# DE-290817_03.net
KiCad netlist of a schematic drawn in Altium Designer
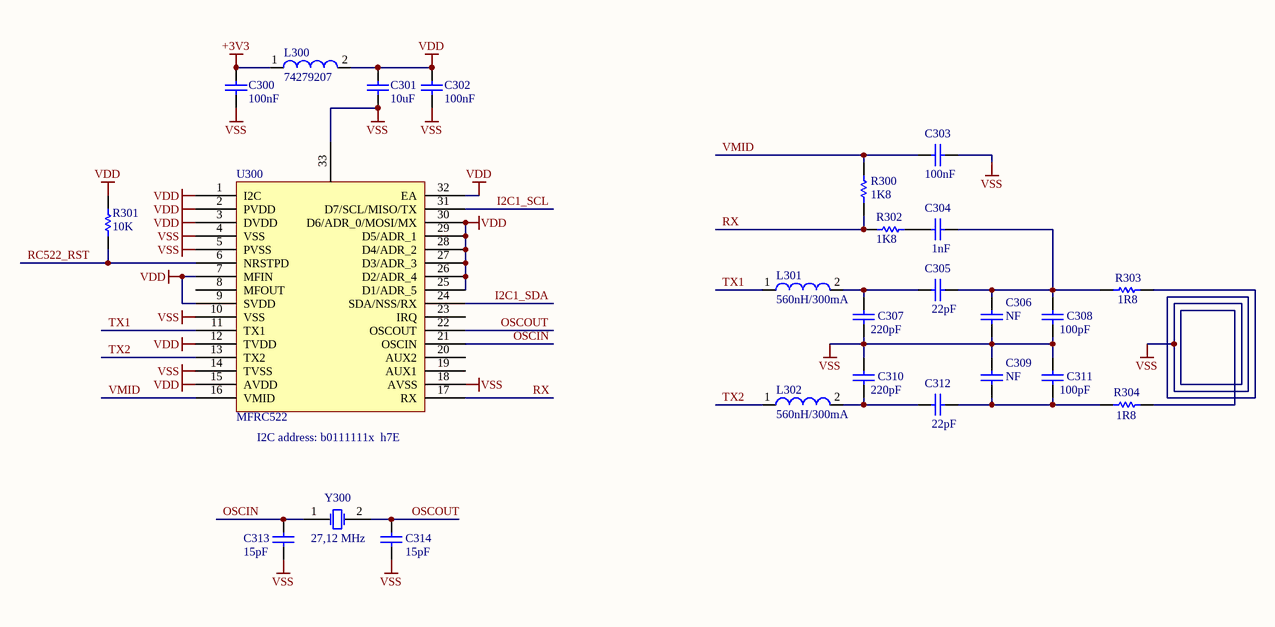
[diagram p0: DE-290817_03.SchDoc]

(export (version "E")
  (design (tool "Eeschema 10.0.6"))
  (components
    (comp (ref "C300")
      (value "100nF")
      (footprint "0603")
      (description "Ceramic Chip Capacitor - Standard")
      (fields (field (name "PUBLISHER") "Altium Limited"))
      (libsource (lib "KEMET Chip Capacitor") (part "C0603"))
    )
    (comp (ref "C301")
      (value "10uF")
      (footprint "0805")
      (description "Ceramic Chip Capacitor - Standard")
      (fields (field (name "PUBLISHER") "Altium Limited"))
      (libsource (lib "KEMET Chip Capacitor") (part "C0805"))
    )
    (comp (ref "C302")
      (value "100nF")
      (footprint "0603")
      (description "Ceramic Chip Capacitor - Standard")
      (fields (field (name "PUBLISHER") "Altium Limited"))
      (libsource (lib "KEMET Chip Capacitor") (part "C0603"))
    )
    (comp (ref "C303")
      (value "100nF")
      (footprint "0603")
      (description "Ceramic Chip Capacitor - Standard")
      (fields (field (name "PUBLISHER") "Altium Limited"))
      (libsource (lib "KEMET Chip Capacitor") (part "C0603"))
    )
    (comp (ref "C304")
      (value "1nF")
      (footprint "0603")
      (description "Ceramic Chip Capacitor - Standard")
      (fields (field (name "PUBLISHER") "Altium Limited"))
      (libsource (lib "KEMET Chip Capacitor") (part "C0603"))
    )
    (comp (ref "C305")
      (value "22pF")
      (footprint "0603")
      (description "Ceramic Chip Capacitor - Standard")
      (fields (field (name "PUBLISHER") "Altium Limited"))
      (libsource (lib "KEMET Chip Capacitor") (part "C0603"))
    )
    (comp (ref "C306")
      (value "NF")
      (footprint "0603")
      (description "Ceramic Chip Capacitor - Standard")
      (fields (field (name "PUBLISHER") "Altium Limited"))
      (libsource (lib "KEMET Chip Capacitor") (part "C0603"))
    )
    (comp (ref "C307")
      (value "220pF")
      (footprint "0603")
      (description "Ceramic Chip Capacitor - Standard")
      (fields (field (name "PUBLISHER") "Altium Limited"))
      (libsource (lib "KEMET Chip Capacitor") (part "C0603"))
    )
    (comp (ref "C308")
      (value "100pF")
      (footprint "0603")
      (description "Ceramic Chip Capacitor - Standard")
      (fields (field (name "PUBLISHER") "Altium Limited"))
      (libsource (lib "KEMET Chip Capacitor") (part "C0603"))
    )
    (comp (ref "C309")
      (value "NF")
      (footprint "0603")
      (description "Ceramic Chip Capacitor - Standard")
      (fields (field (name "PUBLISHER") "Altium Limited"))
      (libsource (lib "KEMET Chip Capacitor") (part "C0603"))
    )
    (comp (ref "C310")
      (value "220pF")
      (footprint "0603")
      (description "Ceramic Chip Capacitor - Standard")
      (fields (field (name "PUBLISHER") "Altium Limited"))
      (libsource (lib "KEMET Chip Capacitor") (part "C0603"))
    )
    (comp (ref "C311")
      (value "100pF")
      (footprint "0603")
      (description "Ceramic Chip Capacitor - Standard")
      (fields (field (name "PUBLISHER") "Altium Limited"))
      (libsource (lib "KEMET Chip Capacitor") (part "C0603"))
    )
    (comp (ref "C312")
      (value "22pF")
      (footprint "0603")
      (description "Ceramic Chip Capacitor - Standard")
      (fields (field (name "PUBLISHER") "Altium Limited"))
      (libsource (lib "KEMET Chip Capacitor") (part "C0603"))
    )
    (comp (ref "C313")
      (value "15pF")
      (footprint "0603")
      (description "Ceramic Chip Capacitor - Standard")
      (fields (field (name "PUBLISHER") "Altium Limited"))
      (libsource (lib "KEMET Chip Capacitor") (part "C0603"))
    )
    (comp (ref "C314")
      (value "15pF")
      (footprint "0603")
      (description "Ceramic Chip Capacitor - Standard")
      (fields (field (name "PUBLISHER") "Altium Limited"))
      (libsource (lib "KEMET Chip Capacitor") (part "C0603"))
    )
    (comp (ref "L300")
      (value "74279207")
      (footprint "SMD-0805")
      (description "SMD EMI Suppression Ferrite Bead WE-CBF, Z = 100 Ohm")
      (libsource (lib "WE-CBF SMD EMI Suppression Ferrite Bead") (part "74279207"))
    )
    (comp (ref "L301")
      (value "560nH/300mA")
      (footprint "SMD-0805")
      (description "SMD EMI Suppression Ferrite Bead WE-CBF, Z = 100 Ohm")
      (fields (field (name "PARTNUMBER") "74279207"))
      (libsource (lib "WE-CBF SMD EMI Suppression Ferrite Bead") (part "74279207"))
    )
    (comp (ref "L302")
      (value "560nH/300mA")
      (footprint "SMD-0805")
      (description "SMD EMI Suppression Ferrite Bead WE-CBF, Z = 100 Ohm")
      (fields (field (name "PARTNUMBER") "74279207"))
      (libsource (lib "WE-CBF SMD EMI Suppression Ferrite Bead") (part "74279207"))
    )
    (comp (ref "R300")
      (value "1K8")
      (footprint "3-0603")
      (fields (field (name "PUBLISHER") "Altium Limited"))
      (libsource (lib "Panasonic Resistor") (part "ERJ3RS"))
    )
    (comp (ref "R301")
      (value "10K")
      (footprint "ERA-0603")
      (fields (field (name "PUBLISHER") "Altium Limited"))
      (libsource (lib "DE-290817") (part "ERAV"))
    )
    (comp (ref "R302")
      (value "1K8")
      (footprint "3-0603")
      (fields (field (name "PUBLISHER") "Altium Limited"))
      (libsource (lib "Panasonic Resistor") (part "ERJ3RS"))
    )
    (comp (ref "R303")
      (value "1R8")
      (footprint "3-0603")
      (fields (field (name "PUBLISHER") "Altium Limited"))
      (libsource (lib "Panasonic Resistor") (part "ERJ3RS"))
    )
    (comp (ref "R304")
      (value "1R8")
      (footprint "3-0603")
      (fields (field (name "PUBLISHER") "Altium Limited"))
      (libsource (lib "Panasonic Resistor") (part "ERJ3RS"))
    )
    (comp (ref "U300")
      (value "MFRC522")
      (footprint "QFN32")
      (description "MIFARE reader writer")
      (libsource (lib "DE-071116") (part "MFRC522"))
    )
    (comp (ref "Y300")
      (value "27,12 MHz")
      (footprint "HC49/4H_SMX")
      (description "Crystal Oscillator")
      (fields (field (name "PUBLISHER") "Altium Limited"))
      (libsource (lib "ECS Crystal Oscillator") (part "ECS-80-20-1"))
    )
  )
  (nets
    (net (code "1") (name "+3V3") (class "Default")
      (node (ref "C300") (pin "2") (pinfunction "2_2") (pintype "passive"))
      (node (ref "L300") (pin "1") (pinfunction "1_1") (pintype "passive"))
    )
    (net (code "2") (name "/I2C1_SCL") (class "Default")
      (node (ref "U300") (pin "31") (pinfunction "D7/SCL/MISO/TX_31") (pintype "passive"))
    )
    (net (code "3") (name "/I2C1_SDA") (class "Default")
      (node (ref "U300") (pin "24") (pinfunction "SDA/NSS/RX_24") (pintype "passive"))
    )
    (net (code "4") (name "/OSCIN") (class "Default")
      (node (ref "C313") (pin "2") (pinfunction "2_2") (pintype "passive"))
      (node (ref "U300") (pin "21") (pinfunction "OSCIN_21") (pintype "passive"))
      (node (ref "Y300") (pin "1") (pinfunction "OSC1_1") (pintype "passive"))
    )
    (net (code "5") (name "/OSCOUT") (class "Default")
      (node (ref "C314") (pin "2") (pinfunction "2_2") (pintype "passive"))
      (node (ref "U300") (pin "22") (pinfunction "OSCOUT_22") (pintype "passive"))
      (node (ref "Y300") (pin "2") (pinfunction "OSC2_2") (pintype "passive"))
    )
    (net (code "6") (name "/RC522_RST") (class "Default")
      (node (ref "R301") (pin "1") (pinfunction "1_1") (pintype "passive"))
      (node (ref "U300") (pin "6") (pinfunction "NRSTPD_6") (pintype "passive"))
    )
    (net (code "7") (name "/RX") (class "Default")
      (node (ref "R300") (pin "2") (pinfunction "2_2") (pintype "passive"))
      (node (ref "R302") (pin "2") (pinfunction "2_2") (pintype "passive"))
      (node (ref "U300") (pin "17") (pinfunction "RX_17") (pintype "passive"))
    )
    (net (code "8") (name "/TX1") (class "Default")
      (node (ref "L301") (pin "1") (pinfunction "1_1") (pintype "passive"))
      (node (ref "U300") (pin "11") (pinfunction "TX1_11") (pintype "passive"))
    )
    (net (code "9") (name "/TX2") (class "Default")
      (node (ref "L302") (pin "1") (pinfunction "1_1") (pintype "passive"))
      (node (ref "U300") (pin "13") (pinfunction "TX2_13") (pintype "passive"))
    )
    (net (code "10") (name "/VMID") (class "Default")
      (node (ref "C303") (pin "2") (pinfunction "2_2") (pintype "passive"))
      (node (ref "R300") (pin "1") (pinfunction "1_1") (pintype "passive"))
      (node (ref "U300") (pin "16") (pinfunction "VMID_16") (pintype "passive"))
    )
    (net (code "11") (name "Net-(C304-Pad1)") (class "Default")
      (node (ref "C304") (pin "1") (pinfunction "1_1") (pintype "passive"))
      (node (ref "C305") (pin "1") (pinfunction "1_1") (pintype "passive"))
      (node (ref "C306") (pin "2") (pinfunction "2_2") (pintype "passive"))
      (node (ref "C308") (pin "2") (pinfunction "2_2") (pintype "passive"))
      (node (ref "R303") (pin "2") (pinfunction "2_2") (pintype "passive"))
    )
    (net (code "12") (name "Net-(C304-Pad2)") (class "Default")
      (node (ref "C304") (pin "2") (pinfunction "2_2") (pintype "passive"))
      (node (ref "R302") (pin "1") (pinfunction "1_1") (pintype "passive"))
    )
    (net (code "13") (name "Net-(C305-Pad2)") (class "Default")
      (node (ref "C305") (pin "2") (pinfunction "2_2") (pintype "passive"))
      (node (ref "C307") (pin "2") (pinfunction "2_2") (pintype "passive"))
      (node (ref "L301") (pin "2") (pinfunction "2_2") (pintype "passive"))
    )
    (net (code "14") (name "Net-(C309-Pad1)") (class "Default")
      (node (ref "C309") (pin "1") (pinfunction "1_1") (pintype "passive"))
      (node (ref "C311") (pin "1") (pinfunction "1_1") (pintype "passive"))
      (node (ref "C312") (pin "1") (pinfunction "1_1") (pintype "passive"))
      (node (ref "R304") (pin "2") (pinfunction "2_2") (pintype "passive"))
    )
    (net (code "15") (name "Net-(C310-Pad1)") (class "Default")
      (node (ref "C310") (pin "1") (pinfunction "1_1") (pintype "passive"))
      (node (ref "C312") (pin "2") (pinfunction "2_2") (pintype "passive"))
      (node (ref "L302") (pin "2") (pinfunction "2_2") (pintype "passive"))
    )
    (net (code "16") (name "VDD") (class "Default")
      (node (ref "C301") (pin "2") (pinfunction "2_2") (pintype "passive"))
      (node (ref "C302") (pin "2") (pinfunction "2_2") (pintype "passive"))
      (node (ref "L300") (pin "2") (pinfunction "2_2") (pintype "passive"))
      (node (ref "R301") (pin "2") (pinfunction "2_2") (pintype "passive"))
      (node (ref "U300") (pin "1") (pinfunction "I2C_1") (pintype "passive"))
      (node (ref "U300") (pin "12") (pinfunction "TVDD_12") (pintype "passive"))
      (node (ref "U300") (pin "15") (pinfunction "AVDD_15") (pintype "passive"))
      (node (ref "U300") (pin "2") (pinfunction "PVDD_2") (pintype "passive"))
      (node (ref "U300") (pin "25") (pinfunction "D1/ADR_5_25") (pintype "passive"))
      (node (ref "U300") (pin "26") (pinfunction "D2/ADR_4_26") (pintype "passive"))
      (node (ref "U300") (pin "27") (pinfunction "D3/ADR_3_27") (pintype "passive"))
      (node (ref "U300") (pin "28") (pinfunction "D4/ADR_2_28") (pintype "passive"))
      (node (ref "U300") (pin "29") (pinfunction "D5/ADR_1_29") (pintype "passive"))
      (node (ref "U300") (pin "3") (pinfunction "DVDD_3") (pintype "passive"))
      (node (ref "U300") (pin "30") (pinfunction "D6/ADR_0/MOSI/MX_30") (pintype "passive"))
      (node (ref "U300") (pin "32") (pinfunction "EA_32") (pintype "passive"))
      (node (ref "U300") (pin "7") (pinfunction "MFIN_7") (pintype "passive"))
      (node (ref "U300") (pin "9") (pinfunction "SVDD_9") (pintype "passive"))
    )
    (net (code "17") (name "VSS") (class "Default")
      (node (ref "C300") (pin "1") (pinfunction "1_1") (pintype "passive"))
      (node (ref "C301") (pin "1") (pinfunction "1_1") (pintype "passive"))
      (node (ref "C302") (pin "1") (pinfunction "1_1") (pintype "passive"))
      (node (ref "C303") (pin "1") (pinfunction "1_1") (pintype "passive"))
      (node (ref "C306") (pin "1") (pinfunction "1_1") (pintype "passive"))
      (node (ref "C307") (pin "1") (pinfunction "1_1") (pintype "passive"))
      (node (ref "C308") (pin "1") (pinfunction "1_1") (pintype "passive"))
      (node (ref "C309") (pin "2") (pinfunction "2_2") (pintype "passive"))
      (node (ref "C310") (pin "2") (pinfunction "2_2") (pintype "passive"))
      (node (ref "C311") (pin "2") (pinfunction "2_2") (pintype "passive"))
      (node (ref "C313") (pin "1") (pinfunction "1_1") (pintype "passive"))
      (node (ref "C314") (pin "1") (pinfunction "1_1") (pintype "passive"))
      (node (ref "R303") (pin "1") (pinfunction "1_1") (pintype "passive"))
      (node (ref "R304") (pin "1") (pinfunction "1_1") (pintype "passive"))
      (node (ref "U300") (pin "10") (pinfunction "VSS_10") (pintype "passive"))
      (node (ref "U300") (pin "14") (pinfunction "TVSS_14") (pintype "passive"))
      (node (ref "U300") (pin "18") (pinfunction "AVSS_18") (pintype "passive"))
      (node (ref "U300") (pin "4") (pinfunction "VSS_4") (pintype "passive"))
      (node (ref "U300") (pin "5") (pinfunction "PVSS_5") (pintype "passive"))
    )
    (net (code "18") (name "unconnected-(U300-AUX1-Pad19)") (class "Default")
      (node (ref "U300") (pin "19") (pinfunction "AUX1_19") (pintype "passive"))
    )
    (net (code "19") (name "unconnected-(U300-AUX2-Pad20)") (class "Default")
      (node (ref "U300") (pin "20") (pinfunction "AUX2_20") (pintype "passive"))
    )
    (net (code "20") (name "unconnected-(U300-IRQ-Pad23)") (class "Default")
      (node (ref "U300") (pin "23") (pinfunction "IRQ_23") (pintype "passive"))
    )
    (net (code "21") (name "unconnected-(U300-MFOUT-Pad8)") (class "Default")
      (node (ref "U300") (pin "8") (pinfunction "MFOUT_8") (pintype "passive"))
    )
    (net (code "22") (name "unconnected-(U300-VSS-Pad33)") (class "Default")
      (node (ref "U300") (pin "33") (pinfunction "VSS_33") (pintype "passive"))
    )
  )
)
